# Fonte1.net
KiCad netlist of a schematic drawn in EAGLE
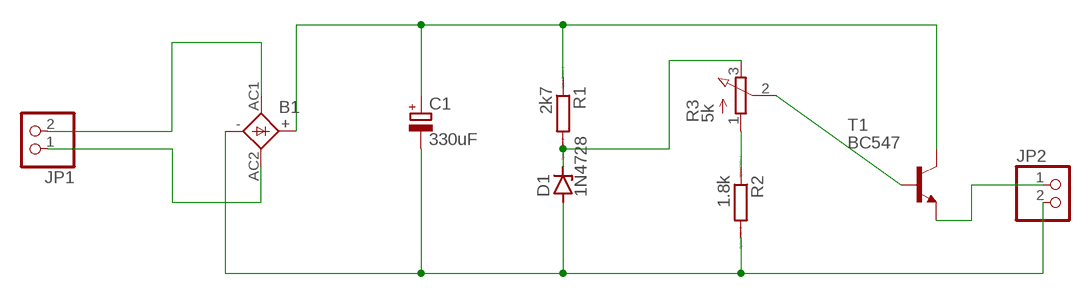
[diagram p0: schematic, sheet 1]

(export (version "E")
  (design (tool "Eeschema 10.0.6"))
  (components
    (comp (ref "B1")
      (value "1KAB")
      (footprint "eagle-import:1KAB")
      (libsource (lib "eagle-import") (part "1KAB"))
    )
    (comp (ref "C1")
      (value "330uF")
      (footprint "eagle-import:E5-10,5")
      (libsource (lib "eagle-import") (part "CPOL-EUE5-10.5"))
    )
    (comp (ref "D1")
      (value "1N4728")
      (footprint "eagle-import:DO41Z10")
      (libsource (lib "eagle-import") (part "1N4728"))
    )
    (comp (ref "JP1")
      (value "PINHD-1X2")
      (footprint "eagle-import:1X02")
      (libsource (lib "eagle-import") (part "PINHD-1X2"))
    )
    (comp (ref "JP2")
      (value "PINHD-1X2")
      (footprint "eagle-import:1X02")
      (libsource (lib "eagle-import") (part "PINHD-1X2"))
    )
    (comp (ref "R1")
      (value "2k7")
      (footprint "eagle-import:0207_10")
      (libsource (lib "eagle-import") (part "R0207/10"))
    )
    (comp (ref "R2")
      (value "1.8k")
      (footprint "eagle-import:0207_10")
      (libsource (lib "eagle-import") (part "R0207/10"))
    )
    (comp (ref "R3")
      (value "5k")
      (footprint "eagle-import:3RP_1610N")
      (libsource (lib "eagle-import") (part "3RP/1610N"))
    )
    (comp (ref "T1")
      (value "BC547")
      (footprint "eagle-import:TO92")
      (libsource (lib "eagle-import") (part "BC547"))
    )
  )
  (nets
    (net (code "1") (name "Net-(B1-Pad-)") (class "Default")
      (node (ref "B1") (pin "-") (pinfunction "-_-") (pintype "passive"))
      (node (ref "C1") (pin "-") (pinfunction "-_-") (pintype "passive"))
      (node (ref "D1") (pin "A") (pinfunction "A_A") (pintype "passive"))
      (node (ref "JP2") (pin "2") (pinfunction "2_2") (pintype "passive"))
      (node (ref "R2") (pin "2") (pinfunction "2_2") (pintype "passive"))
    )
    (net (code "2") (name "Net-(B1-PadAC1)") (class "Default")
      (node (ref "B1") (pin "AC1") (pinfunction "AC1_AC1") (pintype "passive"))
      (node (ref "JP1") (pin "2") (pinfunction "2_2") (pintype "passive"))
    )
    (net (code "3") (name "Net-(B1-PadAC2)") (class "Default")
      (node (ref "B1") (pin "AC2") (pinfunction "AC2_AC2") (pintype "passive"))
      (node (ref "JP1") (pin "1") (pinfunction "1_1") (pintype "passive"))
    )
    (net (code "4") (name "Net-(R3-A)") (class "Default")
      (node (ref "R2") (pin "1") (pinfunction "1_1") (pintype "passive"))
      (node (ref "R3") (pin "1") (pinfunction "A_1") (pintype "passive"))
    )
    (net (code "5") (name "Net-(R3-E)") (class "Default")
      (node (ref "D1") (pin "C") (pinfunction "C_C") (pintype "passive"))
      (node (ref "R1") (pin "2") (pinfunction "2_2") (pintype "passive"))
      (node (ref "R3") (pin "3") (pinfunction "E_3") (pintype "passive"))
    )
    (net (code "6") (name "Net-(R3-S)") (class "Default")
      (node (ref "R3") (pin "2") (pinfunction "S_2") (pintype "passive"))
      (node (ref "T1") (pin "2") (pinfunction "B_2") (pintype "passive"))
    )
    (net (code "7") (name "Net-(T1-C)") (class "Default")
      (node (ref "B1") (pin "+") (pinfunction "+_+") (pintype "passive"))
      (node (ref "C1") (pin "+") (pinfunction "+_+") (pintype "passive"))
      (node (ref "R1") (pin "1") (pinfunction "1_1") (pintype "passive"))
      (node (ref "T1") (pin "3") (pinfunction "C_3") (pintype "passive"))
    )
    (net (code "8") (name "Net-(T1-E)") (class "Default")
      (node (ref "JP2") (pin "1") (pinfunction "1_1") (pintype "passive"))
      (node (ref "T1") (pin "1") (pinfunction "E_1") (pintype "passive"))
    )
  )
)
